# EasyGate1541-II.net
KiCad netlist of a schematic drawn in Altium Designer
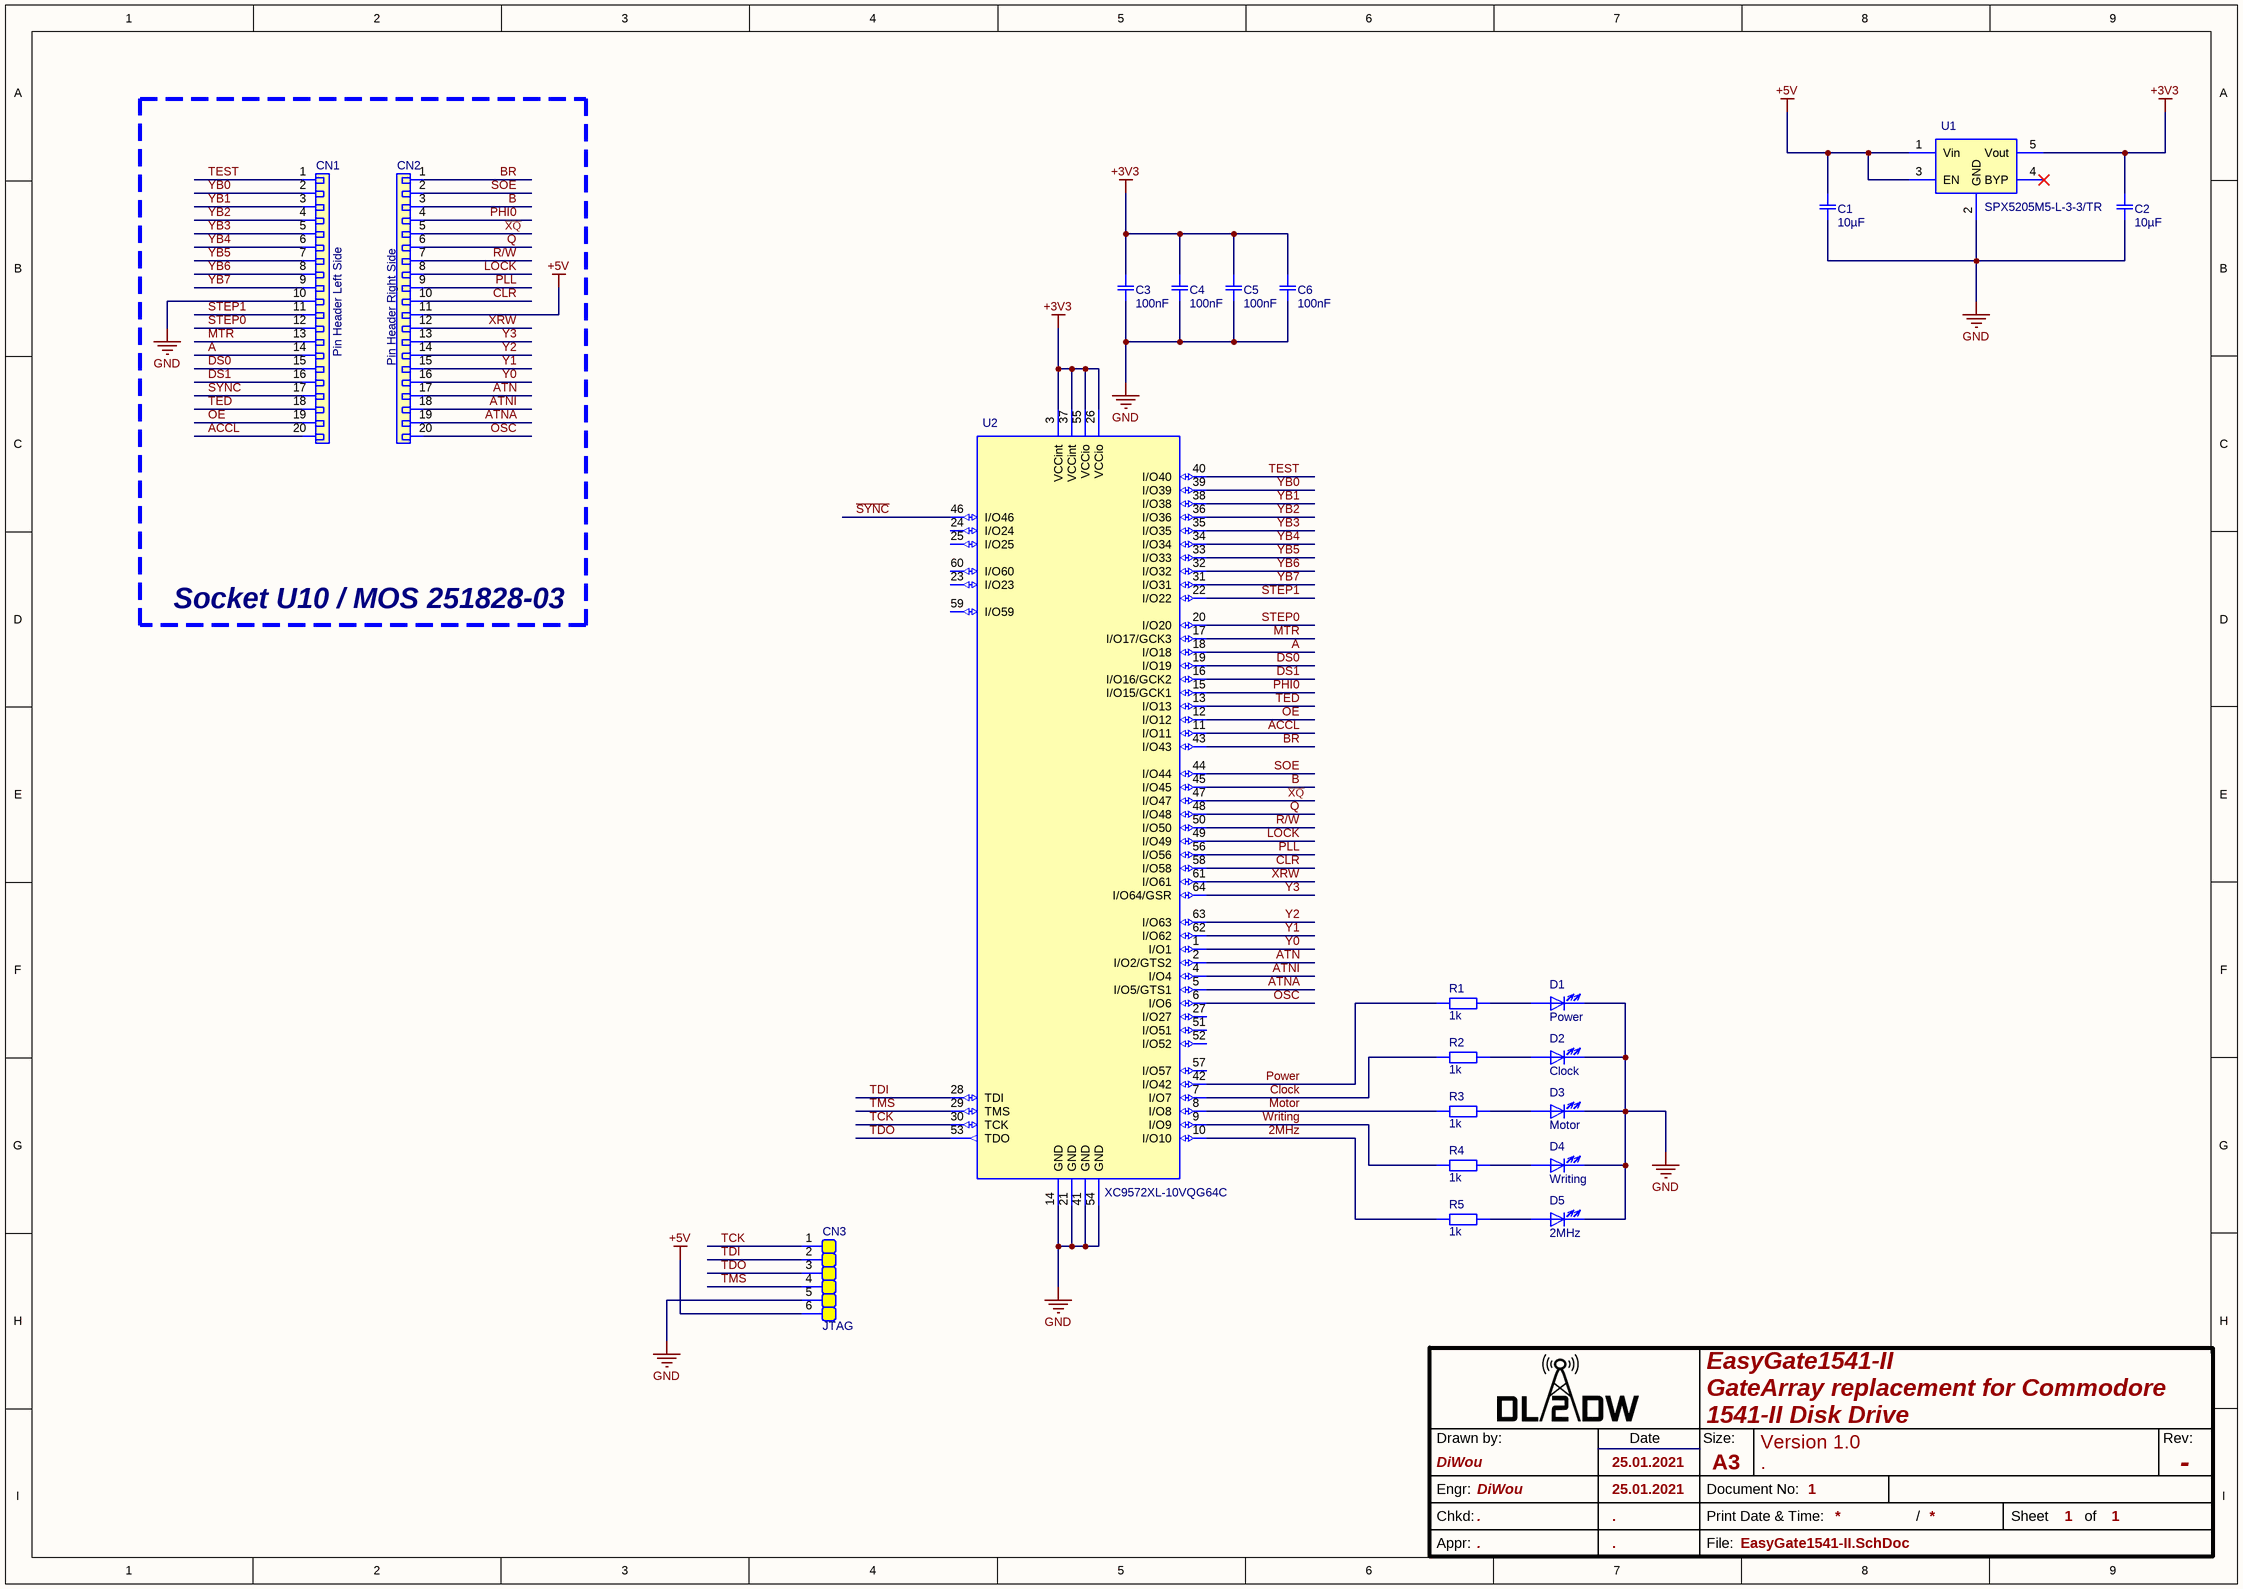
[diagram p0: EasyGate1541-II.SchDoc]

(export (version "E")
  (design (tool "Eeschema 10.0.6"))
  (components
    (comp (ref "C1")
      (value "10µF")
      (footprint "Kemet C0805CxxxK8RACTU Series H=1.4mm")
      (description "KEMET - C0805C106K8RACTU - CAP, 10µF, 10V, 10%, X7R, 0805")
      (fields (field (name "VOLTAGE") "10V") (field (name "TOLERANCE") "10%"))
      (libsource (lib "PCB-Tech Cloud") (part "Capacitor"))
    )
    (comp (ref "C2")
      (value "10µF")
      (footprint "Kemet C0805CxxxK8RACTU Series H=1.4mm")
      (description "KEMET - C0805C106K8RACTU - CAP, 10µF, 10V, 10%, X7R, 0805")
      (fields (field (name "VOLTAGE") "10V") (field (name "TOLERANCE") "10%"))
      (libsource (lib "PCB-Tech Cloud") (part "Capacitor"))
    )
    (comp (ref "C3")
      (value "100nF")
      (footprint "CAP 100nF SMD 0603 C0603C104J3RACTU")
      (fields (field (name "TOLERANCE") "5%") (field (name "VOLTAGE") "25V"))
      (libsource (lib "PCB-Tech Cloud") (part "Capacitor"))
    )
    (comp (ref "C4")
      (value "100nF")
      (footprint "CAP 100nF SMD 0603 C0603C104J3RACTU")
      (fields (field (name "TOLERANCE") "5%") (field (name "VOLTAGE") "25V"))
      (libsource (lib "PCB-Tech Cloud") (part "Capacitor"))
    )
    (comp (ref "C5")
      (value "100nF")
      (footprint "CAP 100nF SMD 0603 C0603C104J3RACTU")
      (fields (field (name "TOLERANCE") "5%") (field (name "VOLTAGE") "25V"))
      (libsource (lib "PCB-Tech Cloud") (part "Capacitor"))
    )
    (comp (ref "C6")
      (value "100nF")
      (footprint "CAP 100nF SMD 0603 C0603C104J3RACTU")
      (fields (field (name "TOLERANCE") "5%") (field (name "VOLTAGE") "25V"))
      (libsource (lib "PCB-Tech Cloud") (part "Capacitor"))
    )
    (comp (ref "CN1")
      (value "Pin Header Left Side")
      (footprint "Pin Header 01x20 2.54mm precision Horizontal Male")
      (description "Conn Header Vert 20POS 2MM")
      (libsource (lib "") (part "CONN 01x20_1"))
    )
    (comp (ref "CN2")
      (value "Pin Header Right Side")
      (footprint "Pin Header 01x20 2.54mm precision Horizontal Male")
      (description "Conn Header Vert 20POS 2MM")
      (libsource (lib "PCB-Tech Cloud") (part "CONN 01x20"))
    )
    (comp (ref "CN3")
      (value "JTAG")
      (footprint "SMD PAD CONN 01x06 small")
      (description "SMD Pad Connector 01x06")
      (libsource (lib "PCB-Tech Cloud") (part "SMD PAD CONN 01x06"))
    )
    (comp (ref "D1")
      (value "Power")
      (footprint "LED green Gullwing Everlight 25-21/GHC-YSU/2A")
      (description "LED Uni-Color Green 518nm 2-Pin Chip LED T/R")
      (libsource (lib "PCB-Tech Cloud") (part "LED Standard"))
    )
    (comp (ref "D2")
      (value "Clock")
      (footprint "LED blue Gullwing Everlight 25-21/BHC-XR2S1/2A")
      (description "LED Uni-Color Blue 468nm Chip LED 2-Pin SMD T/R")
      (libsource (lib "PCB-Tech Cloud") (part "LED Standard"))
    )
    (comp (ref "D3")
      (value "Motor")
      (footprint "LED white Gullwing Everlight 25-21/T1D-ANQHY/2A")
      (description "Standard LEDs - SMD SMD LED")
      (libsource (lib "PCB-Tech Cloud") (part "LED Standard"))
    )
    (comp (ref "D4")
      (value "Writing")
      (footprint "LED red Gullwing Everlight 25-21SURC/S530-A4/TR8")
      (description "SMD LED red 2.7. . .3.15 V Bottom View, 25-21SURC/S530-A4/TR8, Everlight Electronics")
      (libsource (lib "PCB-Tech Cloud") (part "LED Standard"))
    )
    (comp (ref "D5")
      (value "2MHz")
      (footprint "LED white Gullwing Everlight 25-21/T1D-ANQHY/2A")
      (description "Standard LEDs - SMD SMD LED")
      (libsource (lib "PCB-Tech Cloud") (part "LED Standard"))
    )
    (comp (ref "R1")
      (value "1k")
      (footprint "1k Ohm R 0603 SMD")
      (description "RES SMD 1K OHM 1% 1/10W 0603")
      (fields (field (name "TOLERANCE") "1%"))
      (libsource (lib "PCB-Tech Cloud") (part "Resistor"))
    )
    (comp (ref "R2")
      (value "1k")
      (footprint "1k Ohm R 0603 SMD")
      (description "RES SMD 1K OHM 1% 1/10W 0603")
      (fields (field (name "TOLERANCE") "1%"))
      (libsource (lib "PCB-Tech Cloud") (part "Resistor"))
    )
    (comp (ref "R3")
      (value "1k")
      (footprint "1k Ohm R 0603 SMD")
      (description "RES SMD 1K OHM 1% 1/10W 0603")
      (fields (field (name "TOLERANCE") "1%"))
      (libsource (lib "PCB-Tech Cloud") (part "Resistor"))
    )
    (comp (ref "R4")
      (value "1k")
      (footprint "1k Ohm R 0603 SMD")
      (description "RES SMD 1K OHM 1% 1/10W 0603")
      (fields (field (name "TOLERANCE") "1%"))
      (libsource (lib "PCB-Tech Cloud") (part "Resistor"))
    )
    (comp (ref "R5")
      (value "1k")
      (footprint "1k Ohm R 0603 SMD")
      (description "RES SMD 1K OHM 1% 1/10W 0603")
      (fields (field (name "TOLERANCE") "1%"))
      (libsource (lib "PCB-Tech Cloud") (part "Resistor"))
    )
    (comp (ref "U1")
      (value "SPX5205M5-L-3-3/TR")
      (footprint "SOT-23-5")
      (description "LDO Regulator Pos 3.3V 0.15A 5-Pin SOT-23 T/R")
      (libsource (lib "PCB-Tech Cloud") (part "SPX5205M5-L-3-3/TR"))
    )
    (comp (ref "U2")
      (value "XC9572XL-10VQG64C")
      (footprint "XC9572XL-10VQG64")
      (description "IC CPLD 72MC 10NS 64VQFP")
      (libsource (lib "PCB-Tech Cloud") (part "XC9572XL-10VQG64"))
    )
  )
  (nets
    (net (code "1") (name "+3V3") (class "Default")
      (node (ref "C2") (pin "2") (pinfunction "2_2") (pintype "passive"))
      (node (ref "C3") (pin "2") (pinfunction "2_2") (pintype "passive"))
      (node (ref "C4") (pin "2") (pinfunction "2_2") (pintype "passive"))
      (node (ref "C5") (pin "2") (pinfunction "2_2") (pintype "passive"))
      (node (ref "C6") (pin "2") (pinfunction "2_2") (pintype "passive"))
      (node (ref "U1") (pin "5") (pinfunction "Vout_5") (pintype "power_in"))
      (node (ref "U2") (pin "26") (pinfunction "VCCio_26") (pintype "power_in"))
      (node (ref "U2") (pin "3") (pinfunction "VCCint_3") (pintype "power_in"))
      (node (ref "U2") (pin "37") (pinfunction "VCCint_37") (pintype "power_in"))
      (node (ref "U2") (pin "55") (pinfunction "VCCio_55") (pintype "power_in"))
    )
    (net (code "2") (name "+5V") (class "Default")
      (node (ref "C1") (pin "2") (pinfunction "2_2") (pintype "passive"))
      (node (ref "CN2") (pin "11") (pinfunction "11_11") (pintype "passive"))
      (node (ref "CN3") (pin "6") (pinfunction "6_6") (pintype "passive"))
      (node (ref "U1") (pin "1") (pinfunction "Vin_1") (pintype "power_in"))
      (node (ref "U1") (pin "3") (pinfunction "EN_3") (pintype "passive"))
    )
    (net (code "3") (name "/2MHz") (class "Default")
      (node (ref "R5") (pin "1") (pinfunction "1_1") (pintype "passive"))
      (node (ref "U2") (pin "10") (pinfunction "I/O10_10") (pintype "bidirectional"))
    )
    (net (code "4") (name "/ATN") (class "Default")
      (node (ref "CN2") (pin "17") (pinfunction "17_17") (pintype "passive"))
      (node (ref "U2") (pin "2") (pinfunction "I/O2/GTS2_2") (pintype "bidirectional"))
    )
    (net (code "5") (name "/ATNA") (class "Default")
      (node (ref "CN2") (pin "19") (pinfunction "19_19") (pintype "passive"))
      (node (ref "U2") (pin "5") (pinfunction "I/O5/GTS1_5") (pintype "bidirectional"))
    )
    (net (code "6") (name "/ATNI") (class "Default")
      (node (ref "CN2") (pin "18") (pinfunction "18_18") (pintype "passive"))
      (node (ref "U2") (pin "4") (pinfunction "I/O4_4") (pintype "bidirectional"))
    )
    (net (code "7") (name "/B") (class "Default")
      (node (ref "CN2") (pin "3") (pinfunction "3_3") (pintype "passive"))
      (node (ref "U2") (pin "45") (pinfunction "I/O45_45") (pintype "bidirectional"))
    )
    (net (code "8") (name "/BR") (class "Default")
      (node (ref "CN2") (pin "1") (pinfunction "1_1") (pintype "passive"))
      (node (ref "U2") (pin "43") (pinfunction "I/O43_43") (pintype "bidirectional"))
    )
    (net (code "9") (name "/CLR") (class "Default")
      (node (ref "CN2") (pin "10") (pinfunction "10_10") (pintype "passive"))
      (node (ref "U2") (pin "58") (pinfunction "I/O58_58") (pintype "bidirectional"))
    )
    (net (code "10") (name "/Clock") (class "Default")
      (node (ref "R2") (pin "1") (pinfunction "1_1") (pintype "passive"))
      (node (ref "U2") (pin "7") (pinfunction "I/O7_7") (pintype "bidirectional"))
    )
    (net (code "11") (name "/DS0") (class "Default")
      (node (ref "CN1") (pin "15") (pinfunction "15_15") (pintype "passive"))
      (node (ref "U2") (pin "19") (pinfunction "I/O19_19") (pintype "bidirectional"))
    )
    (net (code "12") (name "/DS1") (class "Default")
      (node (ref "CN1") (pin "16") (pinfunction "16_16") (pintype "passive"))
      (node (ref "U2") (pin "16") (pinfunction "I/O16/GCK2_16") (pintype "bidirectional"))
    )
    (net (code "13") (name "/LOCK") (class "Default")
      (node (ref "CN2") (pin "8") (pinfunction "8_8") (pintype "passive"))
      (node (ref "U2") (pin "49") (pinfunction "I/O49_49") (pintype "bidirectional"))
    )
    (net (code "14") (name "/MTR") (class "Default")
      (node (ref "CN1") (pin "13") (pinfunction "13_13") (pintype "passive"))
      (node (ref "U2") (pin "17") (pinfunction "I/O17/GCK3_17") (pintype "bidirectional"))
    )
    (net (code "15") (name "/Motor") (class "Default")
      (node (ref "R3") (pin "1") (pinfunction "1_1") (pintype "passive"))
      (node (ref "U2") (pin "8") (pinfunction "I/O8_8") (pintype "bidirectional"))
    )
    (net (code "16") (name "/OE") (class "Default")
      (node (ref "CN1") (pin "19") (pinfunction "19_19") (pintype "passive"))
      (node (ref "U2") (pin "12") (pinfunction "I/O12_12") (pintype "bidirectional"))
    )
    (net (code "17") (name "/OSC") (class "Default")
      (node (ref "CN2") (pin "20") (pinfunction "20_20") (pintype "passive"))
      (node (ref "U2") (pin "6") (pinfunction "I/O6_6") (pintype "bidirectional"))
    )
    (net (code "18") (name "/PHI0") (class "Default")
      (node (ref "CN2") (pin "4") (pinfunction "4_4") (pintype "passive"))
      (node (ref "U2") (pin "15") (pinfunction "I/O15/GCK1_15") (pintype "bidirectional"))
    )
    (net (code "19") (name "/PLL") (class "Default")
      (node (ref "CN2") (pin "9") (pinfunction "9_9") (pintype "passive"))
      (node (ref "U2") (pin "56") (pinfunction "I/O56_56") (pintype "bidirectional"))
    )
    (net (code "20") (name "/Power") (class "Default")
      (node (ref "R1") (pin "1") (pinfunction "1_1") (pintype "passive"))
      (node (ref "U2") (pin "42") (pinfunction "I/O42_42") (pintype "bidirectional"))
    )
    (net (code "21") (name "/Q") (class "Default")
      (node (ref "CN2") (pin "6") (pinfunction "6_6") (pintype "passive"))
      (node (ref "U2") (pin "48") (pinfunction "I/O48_48") (pintype "bidirectional"))
    )
    (net (code "22") (name "/R{slash}~{W}") (class "Default")
      (node (ref "CN2") (pin "7") (pinfunction "7_7") (pintype "passive"))
      (node (ref "U2") (pin "50") (pinfunction "I/O50_50") (pintype "bidirectional"))
    )
    (net (code "23") (name "/SOE") (class "Default")
      (node (ref "CN2") (pin "2") (pinfunction "2_2") (pintype "passive"))
      (node (ref "U2") (pin "44") (pinfunction "I/O44_44") (pintype "bidirectional"))
    )
    (net (code "24") (name "/STEP0") (class "Default")
      (node (ref "CN1") (pin "12") (pinfunction "12_12") (pintype "passive"))
      (node (ref "U2") (pin "20") (pinfunction "I/O20_20") (pintype "bidirectional"))
    )
    (net (code "25") (name "/STEP1") (class "Default")
      (node (ref "CN1") (pin "11") (pinfunction "11_11") (pintype "passive"))
      (node (ref "U2") (pin "22") (pinfunction "I/O22_22") (pintype "bidirectional"))
    )
    (net (code "26") (name "/TCK") (class "Default")
      (node (ref "CN3") (pin "1") (pinfunction "1_1") (pintype "passive"))
      (node (ref "U2") (pin "30") (pinfunction "TCK_30") (pintype "bidirectional"))
    )
    (net (code "27") (name "/TDI") (class "Default")
      (node (ref "CN3") (pin "2") (pinfunction "2_2") (pintype "passive"))
      (node (ref "U2") (pin "28") (pinfunction "TDI_28") (pintype "bidirectional"))
    )
    (net (code "28") (name "/TDO") (class "Default")
      (node (ref "CN3") (pin "3") (pinfunction "3_3") (pintype "passive"))
      (node (ref "U2") (pin "53") (pinfunction "TDO_53") (pintype "output"))
    )
    (net (code "29") (name "/TED") (class "Default")
      (node (ref "CN1") (pin "18") (pinfunction "18_18") (pintype "passive"))
      (node (ref "U2") (pin "13") (pinfunction "I/O13_13") (pintype "bidirectional"))
    )
    (net (code "30") (name "/TEST") (class "Default")
      (node (ref "CN1") (pin "1") (pinfunction "1_1") (pintype "passive"))
      (node (ref "U2") (pin "40") (pinfunction "I/O40_40") (pintype "bidirectional"))
    )
    (net (code "31") (name "/TMS") (class "Default")
      (node (ref "CN3") (pin "4") (pinfunction "4_4") (pintype "passive"))
      (node (ref "U2") (pin "29") (pinfunction "TMS_29") (pintype "bidirectional"))
    )
    (net (code "32") (name "/Writing") (class "Default")
      (node (ref "R4") (pin "1") (pinfunction "1_1") (pintype "passive"))
      (node (ref "U2") (pin "9") (pinfunction "I/O9_9") (pintype "bidirectional"))
    )
    (net (code "33") (name "/Y0") (class "Default")
      (node (ref "CN2") (pin "16") (pinfunction "16_16") (pintype "passive"))
      (node (ref "U2") (pin "1") (pinfunction "I/O1_1") (pintype "bidirectional"))
    )
    (net (code "34") (name "/Y1") (class "Default")
      (node (ref "CN2") (pin "15") (pinfunction "15_15") (pintype "passive"))
      (node (ref "U2") (pin "62") (pinfunction "I/O62_62") (pintype "bidirectional"))
    )
    (net (code "35") (name "/Y2") (class "Default")
      (node (ref "CN2") (pin "14") (pinfunction "14_14") (pintype "passive"))
      (node (ref "U2") (pin "63") (pinfunction "I/O63_63") (pintype "bidirectional"))
    )
    (net (code "36") (name "/Y3") (class "Default")
      (node (ref "CN2") (pin "13") (pinfunction "13_13") (pintype "passive"))
      (node (ref "U2") (pin "64") (pinfunction "I/O64/GSR_64") (pintype "bidirectional"))
    )
    (net (code "37") (name "/YB0") (class "Default")
      (node (ref "CN1") (pin "2") (pinfunction "2_2") (pintype "passive"))
      (node (ref "U2") (pin "39") (pinfunction "I/O39_39") (pintype "bidirectional"))
    )
    (net (code "38") (name "/YB1") (class "Default")
      (node (ref "CN1") (pin "3") (pinfunction "3_3") (pintype "passive"))
      (node (ref "U2") (pin "38") (pinfunction "I/O38_38") (pintype "bidirectional"))
    )
    (net (code "39") (name "/YB2") (class "Default")
      (node (ref "CN1") (pin "4") (pinfunction "4_4") (pintype "passive"))
      (node (ref "U2") (pin "36") (pinfunction "I/O36_36") (pintype "bidirectional"))
    )
    (net (code "40") (name "/YB3") (class "Default")
      (node (ref "CN1") (pin "5") (pinfunction "5_5") (pintype "passive"))
      (node (ref "U2") (pin "35") (pinfunction "I/O35_35") (pintype "bidirectional"))
    )
    (net (code "41") (name "/YB4") (class "Default")
      (node (ref "CN1") (pin "6") (pinfunction "6_6") (pintype "passive"))
      (node (ref "U2") (pin "34") (pinfunction "I/O34_34") (pintype "bidirectional"))
    )
    (net (code "42") (name "/YB5") (class "Default")
      (node (ref "CN1") (pin "7") (pinfunction "7_7") (pintype "passive"))
      (node (ref "U2") (pin "33") (pinfunction "I/O33_33") (pintype "bidirectional"))
    )
    (net (code "43") (name "/YB6") (class "Default")
      (node (ref "CN1") (pin "8") (pinfunction "8_8") (pintype "passive"))
      (node (ref "U2") (pin "32") (pinfunction "I/O32_32") (pintype "bidirectional"))
    )
    (net (code "44") (name "/YB7") (class "Default")
      (node (ref "CN1") (pin "9") (pinfunction "9_9") (pintype "passive"))
      (node (ref "U2") (pin "31") (pinfunction "I/O31_31") (pintype "bidirectional"))
    )
    (net (code "45") (name "/~{ACCL}") (class "Default")
      (node (ref "CN1") (pin "20") (pinfunction "20_20") (pintype "passive"))
      (node (ref "U2") (pin "11") (pinfunction "I/O11_11") (pintype "bidirectional"))
    )
    (net (code "46") (name "/~{A}") (class "Default")
      (node (ref "CN1") (pin "14") (pinfunction "14_14") (pintype "passive"))
      (node (ref "U2") (pin "18") (pinfunction "I/O18_18") (pintype "bidirectional"))
    )
    (net (code "47") (name "/~{SYNC}") (class "Default")
      (node (ref "CN1") (pin "17") (pinfunction "17_17") (pintype "passive"))
      (node (ref "U2") (pin "46") (pinfunction "I/O46_46") (pintype "bidirectional"))
    )
    (net (code "48") (name "/~{XQ}") (class "Default")
      (node (ref "CN2") (pin "5") (pinfunction "5_5") (pintype "passive"))
      (node (ref "U2") (pin "47") (pinfunction "I/O47_47") (pintype "bidirectional"))
    )
    (net (code "49") (name "/~{XRW}") (class "Default")
      (node (ref "CN2") (pin "12") (pinfunction "12_12") (pintype "passive"))
      (node (ref "U2") (pin "61") (pinfunction "I/O61_61") (pintype "bidirectional"))
    )
    (net (code "50") (name "GND") (class "Default")
      (node (ref "C1") (pin "1") (pinfunction "1_1") (pintype "passive"))
      (node (ref "C2") (pin "1") (pinfunction "1_1") (pintype "passive"))
      (node (ref "C3") (pin "1") (pinfunction "1_1") (pintype "passive"))
      (node (ref "C4") (pin "1") (pinfunction "1_1") (pintype "passive"))
      (node (ref "C5") (pin "1") (pinfunction "1_1") (pintype "passive"))
      (node (ref "C6") (pin "1") (pinfunction "1_1") (pintype "passive"))
      (node (ref "CN1") (pin "10") (pinfunction "10_10") (pintype "passive"))
      (node (ref "CN3") (pin "5") (pinfunction "5_5") (pintype "passive"))
      (node (ref "D1") (pin "1") (pinfunction "1_1") (pintype "passive"))
      (node (ref "D2") (pin "1") (pinfunction "1_1") (pintype "passive"))
      (node (ref "D3") (pin "1") (pinfunction "1_1") (pintype "passive"))
      (node (ref "D4") (pin "1") (pinfunction "1_1") (pintype "passive"))
      (node (ref "D5") (pin "1") (pinfunction "1_1") (pintype "passive"))
      (node (ref "U1") (pin "2") (pinfunction "GND_2") (pintype "power_in"))
      (node (ref "U2") (pin "14") (pinfunction "GND_14") (pintype "power_in"))
      (node (ref "U2") (pin "21") (pinfunction "GND_21") (pintype "power_in"))
      (node (ref "U2") (pin "41") (pinfunction "GND_41") (pintype "power_in"))
      (node (ref "U2") (pin "54") (pinfunction "GND_54") (pintype "power_in"))
    )
    (net (code "51") (name "Net-(D1-Pad2)") (class "Default")
      (node (ref "D1") (pin "2") (pinfunction "2_2") (pintype "passive"))
      (node (ref "R1") (pin "2") (pinfunction "2_2") (pintype "passive"))
    )
    (net (code "52") (name "Net-(D2-Pad2)") (class "Default")
      (node (ref "D2") (pin "2") (pinfunction "2_2") (pintype "passive"))
      (node (ref "R2") (pin "2") (pinfunction "2_2") (pintype "passive"))
    )
    (net (code "53") (name "Net-(D3-Pad2)") (class "Default")
      (node (ref "D3") (pin "2") (pinfunction "2_2") (pintype "passive"))
      (node (ref "R3") (pin "2") (pinfunction "2_2") (pintype "passive"))
    )
    (net (code "54") (name "Net-(D4-Pad2)") (class "Default")
      (node (ref "D4") (pin "2") (pinfunction "2_2") (pintype "passive"))
      (node (ref "R4") (pin "2") (pinfunction "2_2") (pintype "passive"))
    )
    (net (code "55") (name "Net-(D5-Pad2)") (class "Default")
      (node (ref "D5") (pin "2") (pinfunction "2_2") (pintype "passive"))
      (node (ref "R5") (pin "2") (pinfunction "2_2") (pintype "passive"))
    )
    (net (code "56") (name "unconnected-(U1-BYP-Pad4)") (class "Default")
      (node (ref "U1") (pin "4") (pinfunction "BYP_4") (pintype "passive+no_connect"))
    )
    (net (code "57") (name "unconnected-(U2-I{slash}O23-Pad23)") (class "Default")
      (node (ref "U2") (pin "23") (pinfunction "I/O23_23") (pintype "bidirectional"))
    )
    (net (code "58") (name "unconnected-(U2-I{slash}O24-Pad24)") (class "Default")
      (node (ref "U2") (pin "24") (pinfunction "I/O24_24") (pintype "bidirectional"))
    )
    (net (code "59") (name "unconnected-(U2-I{slash}O25-Pad25)") (class "Default")
      (node (ref "U2") (pin "25") (pinfunction "I/O25_25") (pintype "bidirectional"))
    )
    (net (code "60") (name "unconnected-(U2-I{slash}O27-Pad27)") (class "Default")
      (node (ref "U2") (pin "27") (pinfunction "I/O27_27") (pintype "bidirectional"))
    )
    (net (code "61") (name "unconnected-(U2-I{slash}O51-Pad51)") (class "Default")
      (node (ref "U2") (pin "51") (pinfunction "I/O51_51") (pintype "bidirectional"))
    )
    (net (code "62") (name "unconnected-(U2-I{slash}O52-Pad52)") (class "Default")
      (node (ref "U2") (pin "52") (pinfunction "I/O52_52") (pintype "bidirectional"))
    )
    (net (code "63") (name "unconnected-(U2-I{slash}O57-Pad57)") (class "Default")
      (node (ref "U2") (pin "57") (pinfunction "I/O57_57") (pintype "bidirectional"))
    )
    (net (code "64") (name "unconnected-(U2-I{slash}O59-Pad59)") (class "Default")
      (node (ref "U2") (pin "59") (pinfunction "I/O59_59") (pintype "bidirectional"))
    )
    (net (code "65") (name "unconnected-(U2-I{slash}O60-Pad60)") (class "Default")
      (node (ref "U2") (pin "60") (pinfunction "I/O60_60") (pintype "bidirectional"))
    )
  )
)
